# STM32F103RBT6.net
KiCad netlist of a schematic drawn in Altium Designer
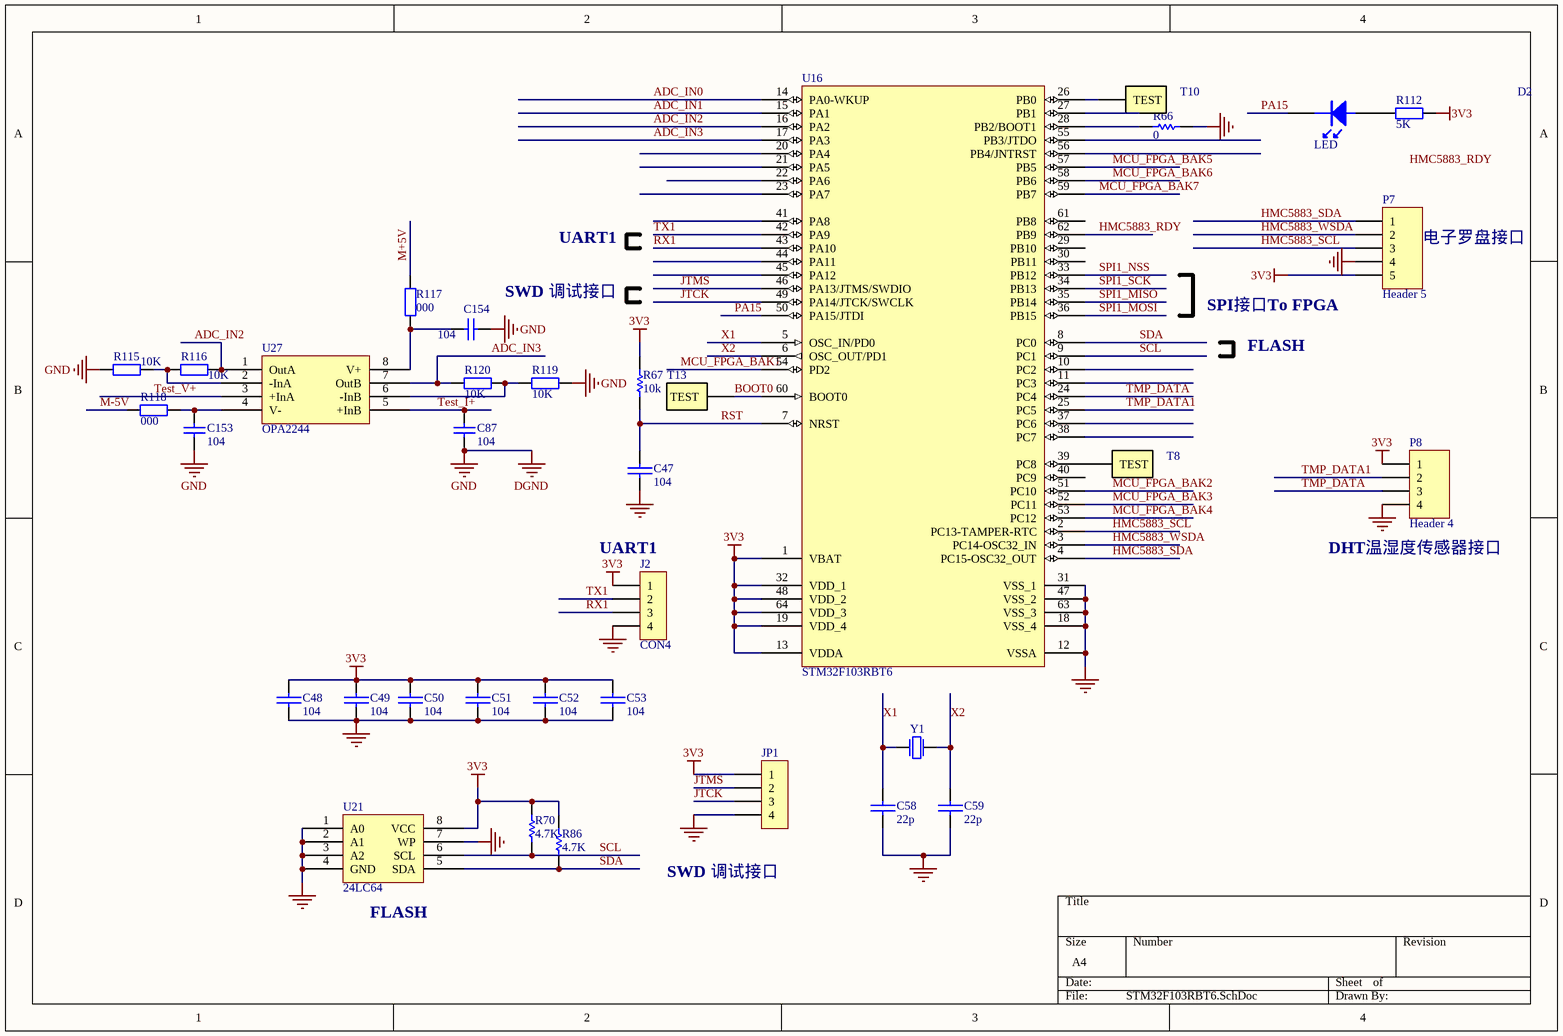
[diagram p0: STM32F103RBT6.SchDoc]

(export (version "E")
  (design (tool "Eeschema 10.0.6"))
  (components
    (comp (ref "C47")
      (value "104")
      (footprint "0603")
      (description "Capacitor")
      (libsource (lib "") (part "CAP_1"))
    )
    (comp (ref "C48")
      (value "104")
      (footprint "0603")
      (description "Capacitor")
      (libsource (lib "*") (part "CAP"))
    )
    (comp (ref "C49")
      (value "104")
      (footprint "0603")
      (description "Capacitor")
      (libsource (lib "*") (part "CAP"))
    )
    (comp (ref "C50")
      (value "104")
      (footprint "0603")
      (description "Capacitor")
      (libsource (lib "*") (part "CAP"))
    )
    (comp (ref "C51")
      (value "104")
      (footprint "0603")
      (description "Capacitor")
      (libsource (lib "*") (part "CAP"))
    )
    (comp (ref "C52")
      (value "104")
      (footprint "0603")
      (description "Capacitor")
      (libsource (lib "*") (part "CAP"))
    )
    (comp (ref "C53")
      (value "104")
      (footprint "0603")
      (description "Capacitor")
      (libsource (lib "*") (part "CAP"))
    )
    (comp (ref "C58")
      (value "22p")
      (footprint "0603")
      (description "Capacitor")
      (libsource (lib "*") (part "CAP"))
    )
    (comp (ref "C59")
      (value "22p")
      (footprint "0603")
      (description "Capacitor")
      (libsource (lib "*") (part "CAP"))
    )
    (comp (ref "C87")
      (value "104")
      (footprint "0603")
      (description "Capacitor")
      (fields (field (name "PUBLISHER") "Altium Limited"))
      (libsource (lib "Miscellaneous Devices") (part "Cap"))
    )
    (comp (ref "C153")
      (value "104")
      (footprint "0603")
      (description "Capacitor")
      (fields (field (name "PUBLISHER") "Altium Limited"))
      (libsource (lib "Miscellaneous Devices") (part "Cap"))
    )
    (comp (ref "C154")
      (value "104")
      (footprint "0603")
      (description "Capacitor")
      (fields (field (name "PUBLISHER") "Altium Limited"))
      (libsource (lib "Miscellaneous Devices") (part "Cap"))
    )
    (comp (ref "D2") (value "LED") (footprint "0805_LED") (libsource (lib "*") (part "LED")))
    (comp (ref "J2")
      (value "CON4")
      (footprint "HDR1X4")
      (description "Connector")
      (libsource (lib "*") (part "CON4"))
    )
    (comp (ref "JP1")
      (value "~")
      (footprint "HDR1X4")
      (description "Connector")
      (libsource (lib "*") (part "CON4"))
    )
    (comp (ref "P7")
      (value "Header 5")
      (footprint "HDR1X5")
      (description "Header, 5-Pin")
      (fields (field (name "PUBLISHER") "Altium Limited"))
      (libsource (lib "Miscellaneous Connectors") (part "Header 5"))
    )
    (comp (ref "P8")
      (value "Header 4")
      (footprint "HDR1X4")
      (description "Header, 4-Pin")
      (fields (field (name "PUBLISHER") "Altium Limited"))
      (libsource (lib "Miscellaneous Connectors") (part "Header 4"))
    )
    (comp (ref "R66")
      (value "0")
      (footprint "0603")
      (description "Resistor")
      (fields (field (name "PUBLISHER") "*"))
      (libsource (lib "*") (part "Res1"))
    )
    (comp (ref "R67")
      (value "10k")
      (footprint "0603")
      (description "Resistor")
      (fields (field (name "PUBLISHER") "*"))
      (libsource (lib "*") (part "res1"))
    )
    (comp (ref "R70")
      (value "4.7K")
      (footprint "0603")
      (description "Resistor")
      (fields (field (name "PUBLISHER") "*"))
      (libsource (lib "*") (part "Res1"))
    )
    (comp (ref "R86")
      (value "4.7K")
      (footprint "0603")
      (description "Resistor")
      (fields (field (name "PUBLISHER") "*"))
      (libsource (lib "*") (part "Res1"))
    )
    (comp (ref "R112")
      (value "5K")
      (footprint "0603")
      (description "Resistor")
      (fields (field (name "Comment") "Res2") (field (name "PUBLISHER") "Altium Limited"))
      (libsource (lib "") (part "Res2_1"))
    )
    (comp (ref "R115")
      (value "10K")
      (footprint "0603")
      (description "Resistor")
      (fields (field (name "Comment") "Res2") (field (name "PUBLISHER") "Altium Limited"))
      (libsource (lib "") (part "Res2_1"))
    )
    (comp (ref "R116")
      (value "10K")
      (footprint "0603")
      (description "Resistor")
      (fields (field (name "Comment") "Res2") (field (name "PUBLISHER") "Altium Limited"))
      (libsource (lib "") (part "Res2_1"))
    )
    (comp (ref "R117")
      (value "000")
      (footprint "0805R")
      (description "Resistor")
      (fields (field (name "PUBLISHER") "Altium Limited"))
      (libsource (lib "") (part "Res2_2"))
    )
    (comp (ref "R118")
      (value "000")
      (footprint "0805R")
      (description "Resistor")
      (fields (field (name "PUBLISHER") "Altium Limited"))
      (libsource (lib "Miscellaneous Devices") (part "Res2"))
    )
    (comp (ref "R119")
      (value "10K")
      (footprint "0603")
      (description "Resistor")
      (fields (field (name "Comment") "Res2") (field (name "PUBLISHER") "Altium Limited"))
      (libsource (lib "Miscellaneous Devices") (part "Res2"))
    )
    (comp (ref "R120")
      (value "10K")
      (footprint "0603")
      (description "Resistor")
      (fields (field (name "Comment") "Res2") (field (name "PUBLISHER") "Altium Limited"))
      (libsource (lib "Miscellaneous Devices") (part "Res2"))
    )
    (comp (ref "T8") (value "~") (footprint "TEST") (libsource (lib "USB30_Project") (part "TEST")))
    (comp (ref "T10") (value "~") (footprint "TEST") (libsource (lib "USB30_Project") (part "TEST")))
    (comp (ref "T13") (value "~") (footprint "TEST") (libsource (lib "") (part "TEST_1")))
    (comp (ref "U16")
      (value "STM32F103RBT6")
      (footprint "LQFP64_M")
      (description "STM32 ARM-based 32-bit MCU with 128 Kbytes Flash, 64-pin LQFP, Industrial Temperature")
      (fields (field (name "PUBLISHER") "*"))
      (libsource (lib "*") (part "STM32F103RBT6"))
    )
    (comp (ref "U21") (value "24LC64") (footprint "SO8") (libsource (lib "*") (part "24C02")))
    (comp (ref "U27") (value "OPA2244") (footprint "SO8") (libsource (lib "Schlib1") (part "OPA2244")))
    (comp (ref "Y1")
      (value "~")
      (footprint "XTAL_8M")
      (description "Crystal Oscillator")
      (libsource (lib "*") (part "XTAL"))
    )
  )
  (nets
    (net (code "1") (name "/ADC_IN0") (class "Default")
      (node (ref "U16") (pin "14") (pinfunction "PA0-WKUP_14") (pintype "bidirectional"))
    )
    (net (code "2") (name "/ADC_IN1") (class "Default")
      (node (ref "U16") (pin "15") (pinfunction "PA1_15") (pintype "bidirectional"))
    )
    (net (code "3") (name "/ADC_IN2") (class "Default")
      (node (ref "R116") (pin "2") (pinfunction "2_2") (pintype "passive"))
      (node (ref "U16") (pin "16") (pinfunction "PA2_16") (pintype "bidirectional"))
      (node (ref "U27") (pin "1") (pinfunction "OutA_1") (pintype "passive"))
    )
    (net (code "4") (name "/ADC_IN3") (class "Default")
      (node (ref "R120") (pin "2") (pinfunction "2_2") (pintype "passive"))
      (node (ref "U16") (pin "17") (pinfunction "PA3_17") (pintype "bidirectional"))
      (node (ref "U27") (pin "7") (pinfunction "OutB_7") (pintype "passive"))
    )
    (net (code "5") (name "/BOOT0") (class "Default")
      (node (ref "T13") (pin "1") (pinfunction "TEST_1") (pintype "passive"))
      (node (ref "U16") (pin "60") (pinfunction "BOOT0_60") (pintype "input"))
    )
    (net (code "6") (name "/HMC5883_RDY") (class "Default")
      (node (ref "U16") (pin "62") (pinfunction "PB9_62") (pintype "bidirectional"))
    )
    (net (code "7") (name "/HMC5883_SCL") (class "Default")
      (node (ref "P7") (pin "3") (pinfunction "3_3") (pintype "passive"))
      (node (ref "U16") (pin "2") (pinfunction "PC13-TAMPER-RTC_2") (pintype "bidirectional"))
    )
    (net (code "8") (name "/HMC5883_SDA") (class "Default")
      (node (ref "P7") (pin "1") (pinfunction "1_1") (pintype "passive"))
      (node (ref "U16") (pin "4") (pinfunction "PC15-OSC32_OUT_4") (pintype "bidirectional"))
    )
    (net (code "9") (name "/HMC5883_WSDA") (class "Default")
      (node (ref "P7") (pin "2") (pinfunction "2_2") (pintype "passive"))
      (node (ref "U16") (pin "3") (pinfunction "PC14-OSC32_IN_3") (pintype "bidirectional"))
    )
    (net (code "10") (name "/JTCK") (class "Default")
      (node (ref "JP1") (pin "3") (pinfunction "3_3") (pintype "passive"))
      (node (ref "U16") (pin "49") (pinfunction "PA14/JTCK/SWCLK_49") (pintype "bidirectional"))
    )
    (net (code "11") (name "/JTMS") (class "Default")
      (node (ref "JP1") (pin "2") (pinfunction "2_2") (pintype "passive"))
      (node (ref "U16") (pin "46") (pinfunction "PA13/JTMS/SWDIO_46") (pintype "bidirectional"))
    )
    (net (code "12") (name "/M+5V") (class "Default")
      (node (ref "R117") (pin "1") (pinfunction "1_1") (pintype "passive"))
    )
    (net (code "13") (name "/M-5V") (class "Default")
      (node (ref "R118") (pin "2") (pinfunction "2_2") (pintype "passive"))
    )
    (net (code "14") (name "/MCU_FPGA_BAK1") (class "Default")
      (node (ref "U16") (pin "54") (pinfunction "PD2_54") (pintype "bidirectional"))
    )
    (net (code "15") (name "/MCU_FPGA_BAK2") (class "Default")
      (node (ref "U16") (pin "51") (pinfunction "PC10_51") (pintype "bidirectional"))
    )
    (net (code "16") (name "/MCU_FPGA_BAK3") (class "Default")
      (node (ref "U16") (pin "52") (pinfunction "PC11_52") (pintype "bidirectional"))
    )
    (net (code "17") (name "/MCU_FPGA_BAK4") (class "Default")
      (node (ref "U16") (pin "53") (pinfunction "PC12_53") (pintype "bidirectional"))
    )
    (net (code "18") (name "/MCU_FPGA_BAK5") (class "Default")
      (node (ref "U16") (pin "57") (pinfunction "PB5_57") (pintype "bidirectional"))
    )
    (net (code "19") (name "/MCU_FPGA_BAK6") (class "Default")
      (node (ref "U16") (pin "58") (pinfunction "PB6_58") (pintype "bidirectional"))
    )
    (net (code "20") (name "/MCU_FPGA_BAK7") (class "Default")
      (node (ref "U16") (pin "59") (pinfunction "PB7_59") (pintype "bidirectional"))
    )
    (net (code "21") (name "/PA15") (class "Default")
      (node (ref "D2") (pin "2") (pinfunction "K_2") (pintype "passive"))
      (node (ref "U16") (pin "50") (pinfunction "PA15/JTDI_50") (pintype "bidirectional"))
    )
    (net (code "22") (name "/RST") (class "Default")
      (node (ref "C47") (pin "1") (pinfunction "1_1") (pintype "passive"))
      (node (ref "R67") (pin "1") (pinfunction "1_1") (pintype "passive"))
      (node (ref "U16") (pin "7") (pinfunction "NRST_7") (pintype "bidirectional"))
    )
    (net (code "23") (name "/RX1") (class "Default")
      (node (ref "J2") (pin "3") (pinfunction "3_3") (pintype "passive"))
      (node (ref "U16") (pin "43") (pinfunction "PA10_43") (pintype "bidirectional"))
    )
    (net (code "24") (name "/SCL") (class "Default")
      (node (ref "R70") (pin "1") (pinfunction "1_1") (pintype "passive"))
      (node (ref "U16") (pin "9") (pinfunction "PC1_9") (pintype "bidirectional"))
      (node (ref "U21") (pin "6") (pinfunction "SCL_6") (pintype "passive"))
    )
    (net (code "25") (name "/SDA") (class "Default")
      (node (ref "R86") (pin "1") (pinfunction "1_1") (pintype "passive"))
      (node (ref "U16") (pin "8") (pinfunction "PC0_8") (pintype "bidirectional"))
      (node (ref "U21") (pin "5") (pinfunction "SDA_5") (pintype "passive"))
    )
    (net (code "26") (name "/SPI1_MISO") (class "Default")
      (node (ref "U16") (pin "35") (pinfunction "PB14_35") (pintype "bidirectional"))
    )
    (net (code "27") (name "/SPI1_MOSI") (class "Default")
      (node (ref "U16") (pin "36") (pinfunction "PB15_36") (pintype "bidirectional"))
    )
    (net (code "28") (name "/SPI1_NSS") (class "Default")
      (node (ref "U16") (pin "33") (pinfunction "PB12_33") (pintype "bidirectional"))
    )
    (net (code "29") (name "/SPI1_SCK") (class "Default")
      (node (ref "U16") (pin "34") (pinfunction "PB13_34") (pintype "bidirectional"))
    )
    (net (code "30") (name "/TMP_DATA") (class "Default")
      (node (ref "P8") (pin "3") (pinfunction "3_3") (pintype "passive"))
      (node (ref "U16") (pin "24") (pinfunction "PC4_24") (pintype "bidirectional"))
    )
    (net (code "31") (name "/TMP_DATA1") (class "Default")
      (node (ref "P8") (pin "2") (pinfunction "2_2") (pintype "passive"))
      (node (ref "U16") (pin "25") (pinfunction "PC5_25") (pintype "bidirectional"))
    )
    (net (code "32") (name "/TX1") (class "Default")
      (node (ref "J2") (pin "2") (pinfunction "2_2") (pintype "passive"))
      (node (ref "U16") (pin "42") (pinfunction "PA9_42") (pintype "bidirectional"))
    )
    (net (code "33") (name "/Test_I+") (class "Default")
      (node (ref "C87") (pin "2") (pinfunction "2_2") (pintype "passive"))
      (node (ref "U27") (pin "5") (pinfunction "+InB_5") (pintype "passive"))
    )
    (net (code "34") (name "/Test_V+") (class "Default")
      (node (ref "U27") (pin "3") (pinfunction "+InA_3") (pintype "passive"))
    )
    (net (code "35") (name "/X1") (class "Default")
      (node (ref "C58") (pin "1") (pinfunction "1_1") (pintype "passive"))
      (node (ref "U16") (pin "5") (pinfunction "OSC_IN/PD0_5") (pintype "input"))
      (node (ref "Y1") (pin "2") (pinfunction "P2_2") (pintype "passive"))
    )
    (net (code "36") (name "/X2") (class "Default")
      (node (ref "C59") (pin "1") (pinfunction "1_1") (pintype "passive"))
      (node (ref "U16") (pin "6") (pinfunction "OSC_OUT/PD1_6") (pintype "output"))
      (node (ref "Y1") (pin "1") (pinfunction "P1_1") (pintype "passive"))
    )
    (net (code "37") (name "3V3") (class "Default")
      (node (ref "C48") (pin "1") (pinfunction "1_1") (pintype "passive"))
      (node (ref "C49") (pin "1") (pinfunction "1_1") (pintype "passive"))
      (node (ref "C50") (pin "1") (pinfunction "1_1") (pintype "passive"))
      (node (ref "C51") (pin "1") (pinfunction "1_1") (pintype "passive"))
      (node (ref "C52") (pin "1") (pinfunction "1_1") (pintype "passive"))
      (node (ref "C53") (pin "1") (pinfunction "1_1") (pintype "passive"))
      (node (ref "J2") (pin "1") (pinfunction "1_1") (pintype "passive"))
      (node (ref "JP1") (pin "1") (pinfunction "1_1") (pintype "passive"))
      (node (ref "P7") (pin "5") (pinfunction "5_5") (pintype "passive"))
      (node (ref "P8") (pin "1") (pinfunction "1_1") (pintype "passive"))
      (node (ref "R112") (pin "2") (pinfunction "2_2") (pintype "passive"))
      (node (ref "R67") (pin "2") (pinfunction "2_2") (pintype "passive"))
      (node (ref "R70") (pin "2") (pinfunction "2_2") (pintype "passive"))
      (node (ref "R86") (pin "2") (pinfunction "2_2") (pintype "passive"))
      (node (ref "U16") (pin "1") (pinfunction "VBAT_1") (pintype "power_in"))
      (node (ref "U16") (pin "13") (pinfunction "VDDA_13") (pintype "power_in"))
      (node (ref "U16") (pin "19") (pinfunction "VDD_4_19") (pintype "power_in"))
      (node (ref "U16") (pin "32") (pinfunction "VDD_1_32") (pintype "power_in"))
      (node (ref "U16") (pin "48") (pinfunction "VDD_2_48") (pintype "power_in"))
      (node (ref "U16") (pin "64") (pinfunction "VDD_3_64") (pintype "power_in"))
      (node (ref "U21") (pin "8") (pinfunction "VCC_8") (pintype "passive"))
    )
    (net (code "38") (name "DGND") (class "Default")
      (node (ref "C153") (pin "1") (pinfunction "1_1") (pintype "passive"))
      (node (ref "C154") (pin "2") (pinfunction "2_2") (pintype "passive"))
      (node (ref "C47") (pin "2") (pinfunction "2_2") (pintype "passive"))
      (node (ref "C48") (pin "2") (pinfunction "2_2") (pintype "passive"))
      (node (ref "C49") (pin "2") (pinfunction "2_2") (pintype "passive"))
      (node (ref "C50") (pin "2") (pinfunction "2_2") (pintype "passive"))
      (node (ref "C51") (pin "2") (pinfunction "2_2") (pintype "passive"))
      (node (ref "C52") (pin "2") (pinfunction "2_2") (pintype "passive"))
      (node (ref "C53") (pin "2") (pinfunction "2_2") (pintype "passive"))
      (node (ref "C58") (pin "2") (pinfunction "2_2") (pintype "passive"))
      (node (ref "C59") (pin "2") (pinfunction "2_2") (pintype "passive"))
      (node (ref "C87") (pin "1") (pinfunction "1_1") (pintype "passive"))
      (node (ref "J2") (pin "4") (pinfunction "4_4") (pintype "passive"))
      (node (ref "JP1") (pin "4") (pinfunction "4_4") (pintype "passive"))
      (node (ref "P7") (pin "4") (pinfunction "4_4") (pintype "passive"))
      (node (ref "P8") (pin "4") (pinfunction "4_4") (pintype "passive"))
      (node (ref "R115") (pin "1") (pinfunction "1_1") (pintype "passive"))
      (node (ref "R119") (pin "1") (pinfunction "1_1") (pintype "passive"))
      (node (ref "R66") (pin "2") (pinfunction "2_2") (pintype "passive"))
      (node (ref "U16") (pin "12") (pinfunction "VSSA_12") (pintype "power_in"))
      (node (ref "U16") (pin "18") (pinfunction "VSS_4_18") (pintype "power_in"))
      (node (ref "U16") (pin "31") (pinfunction "VSS_1_31") (pintype "power_in"))
      (node (ref "U16") (pin "47") (pinfunction "VSS_2_47") (pintype "power_in"))
      (node (ref "U16") (pin "63") (pinfunction "VSS_3_63") (pintype "power_in"))
      (node (ref "U21") (pin "1") (pinfunction "A0_1") (pintype "passive"))
      (node (ref "U21") (pin "2") (pinfunction "A1_2") (pintype "passive"))
      (node (ref "U21") (pin "3") (pinfunction "A2_3") (pintype "passive"))
      (node (ref "U21") (pin "4") (pinfunction "GND_4") (pintype "passive"))
      (node (ref "U21") (pin "7") (pinfunction "WP_7") (pintype "passive"))
    )
    (net (code "39") (name "Net-(D2-A)") (class "Default")
      (node (ref "D2") (pin "1") (pinfunction "A_1") (pintype "passive"))
      (node (ref "R112") (pin "1") (pinfunction "1_1") (pintype "passive"))
    )
    (net (code "40") (name "Net-(T8-TEST)") (class "Default")
      (node (ref "T8") (pin "1") (pinfunction "TEST_1") (pintype "passive"))
      (node (ref "U16") (pin "39") (pinfunction "PC8_39") (pintype "bidirectional"))
    )
    (net (code "41") (name "Net-(T10-TEST)") (class "Default")
      (node (ref "T10") (pin "1") (pinfunction "TEST_1") (pintype "passive"))
      (node (ref "U16") (pin "26") (pinfunction "PB0_26") (pintype "bidirectional"))
    )
    (net (code "42") (name "Net-(U16-PB2{slash}BOOT1)") (class "Default")
      (node (ref "R66") (pin "1") (pinfunction "1_1") (pintype "passive"))
      (node (ref "U16") (pin "28") (pinfunction "PB2/BOOT1_28") (pintype "bidirectional"))
    )
    (net (code "43") (name "Net-(U27--InA)") (class "Default")
      (node (ref "R115") (pin "2") (pinfunction "2_2") (pintype "passive"))
      (node (ref "R116") (pin "1") (pinfunction "1_1") (pintype "passive"))
      (node (ref "U27") (pin "2") (pinfunction "-InA_2") (pintype "passive"))
    )
    (net (code "44") (name "Net-(U27--InB)") (class "Default")
      (node (ref "R119") (pin "2") (pinfunction "2_2") (pintype "passive"))
      (node (ref "R120") (pin "1") (pinfunction "1_1") (pintype "passive"))
      (node (ref "U27") (pin "6") (pinfunction "-InB_6") (pintype "passive"))
    )
    (net (code "45") (name "Net-(U27-V+)") (class "Default")
      (node (ref "C154") (pin "1") (pinfunction "1_1") (pintype "passive"))
      (node (ref "R117") (pin "2") (pinfunction "2_2") (pintype "passive"))
      (node (ref "U27") (pin "8") (pinfunction "V+_8") (pintype "passive"))
    )
    (net (code "46") (name "Net-(U27-V-)") (class "Default")
      (node (ref "C153") (pin "2") (pinfunction "2_2") (pintype "passive"))
      (node (ref "R118") (pin "1") (pinfunction "1_1") (pintype "passive"))
      (node (ref "U27") (pin "4") (pinfunction "V-_4") (pintype "passive"))
    )
    (net (code "47") (name "unconnected-(U16-PA4-Pad20)") (class "Default")
      (node (ref "U16") (pin "20") (pinfunction "PA4_20") (pintype "bidirectional"))
    )
    (net (code "48") (name "unconnected-(U16-PA5-Pad21)") (class "Default")
      (node (ref "U16") (pin "21") (pinfunction "PA5_21") (pintype "bidirectional"))
    )
    (net (code "49") (name "unconnected-(U16-PA6-Pad22)") (class "Default")
      (node (ref "U16") (pin "22") (pinfunction "PA6_22") (pintype "bidirectional"))
    )
    (net (code "50") (name "unconnected-(U16-PA7-Pad23)") (class "Default")
      (node (ref "U16") (pin "23") (pinfunction "PA7_23") (pintype "bidirectional"))
    )
    (net (code "51") (name "unconnected-(U16-PA8-Pad41)") (class "Default")
      (node (ref "U16") (pin "41") (pinfunction "PA8_41") (pintype "bidirectional"))
    )
    (net (code "52") (name "unconnected-(U16-PA11-Pad44)") (class "Default")
      (node (ref "U16") (pin "44") (pinfunction "PA11_44") (pintype "bidirectional"))
    )
    (net (code "53") (name "unconnected-(U16-PA12-Pad45)") (class "Default")
      (node (ref "U16") (pin "45") (pinfunction "PA12_45") (pintype "bidirectional"))
    )
    (net (code "54") (name "unconnected-(U16-PB1-Pad27)") (class "Default")
      (node (ref "U16") (pin "27") (pinfunction "PB1_27") (pintype "bidirectional"))
    )
    (net (code "55") (name "unconnected-(U16-PB3{slash}JTDO-Pad55)") (class "Default")
      (node (ref "U16") (pin "55") (pinfunction "PB3/JTDO_55") (pintype "bidirectional"))
    )
    (net (code "56") (name "unconnected-(U16-PB4{slash}JNTRST-Pad56)") (class "Default")
      (node (ref "U16") (pin "56") (pinfunction "PB4/JNTRST_56") (pintype "bidirectional"))
    )
    (net (code "57") (name "unconnected-(U16-PB8-Pad61)") (class "Default")
      (node (ref "U16") (pin "61") (pinfunction "PB8_61") (pintype "bidirectional"))
    )
    (net (code "58") (name "unconnected-(U16-PB10-Pad29)") (class "Default")
      (node (ref "U16") (pin "29") (pinfunction "PB10_29") (pintype "bidirectional"))
    )
    (net (code "59") (name "unconnected-(U16-PB11-Pad30)") (class "Default")
      (node (ref "U16") (pin "30") (pinfunction "PB11_30") (pintype "bidirectional"))
    )
    (net (code "60") (name "unconnected-(U16-PC2-Pad10)") (class "Default")
      (node (ref "U16") (pin "10") (pinfunction "PC2_10") (pintype "bidirectional"))
    )
    (net (code "61") (name "unconnected-(U16-PC3-Pad11)") (class "Default")
      (node (ref "U16") (pin "11") (pinfunction "PC3_11") (pintype "bidirectional"))
    )
    (net (code "62") (name "unconnected-(U16-PC6-Pad37)") (class "Default")
      (node (ref "U16") (pin "37") (pinfunction "PC6_37") (pintype "bidirectional"))
    )
    (net (code "63") (name "unconnected-(U16-PC7-Pad38)") (class "Default")
      (node (ref "U16") (pin "38") (pinfunction "PC7_38") (pintype "bidirectional"))
    )
    (net (code "64") (name "unconnected-(U16-PC9-Pad40)") (class "Default")
      (node (ref "U16") (pin "40") (pinfunction "PC9_40") (pintype "bidirectional"))
    )
  )
)
